# SCH_projecthackclub_2024-11-15.net
KiCad netlist of a schematic drawn in EasyEDA
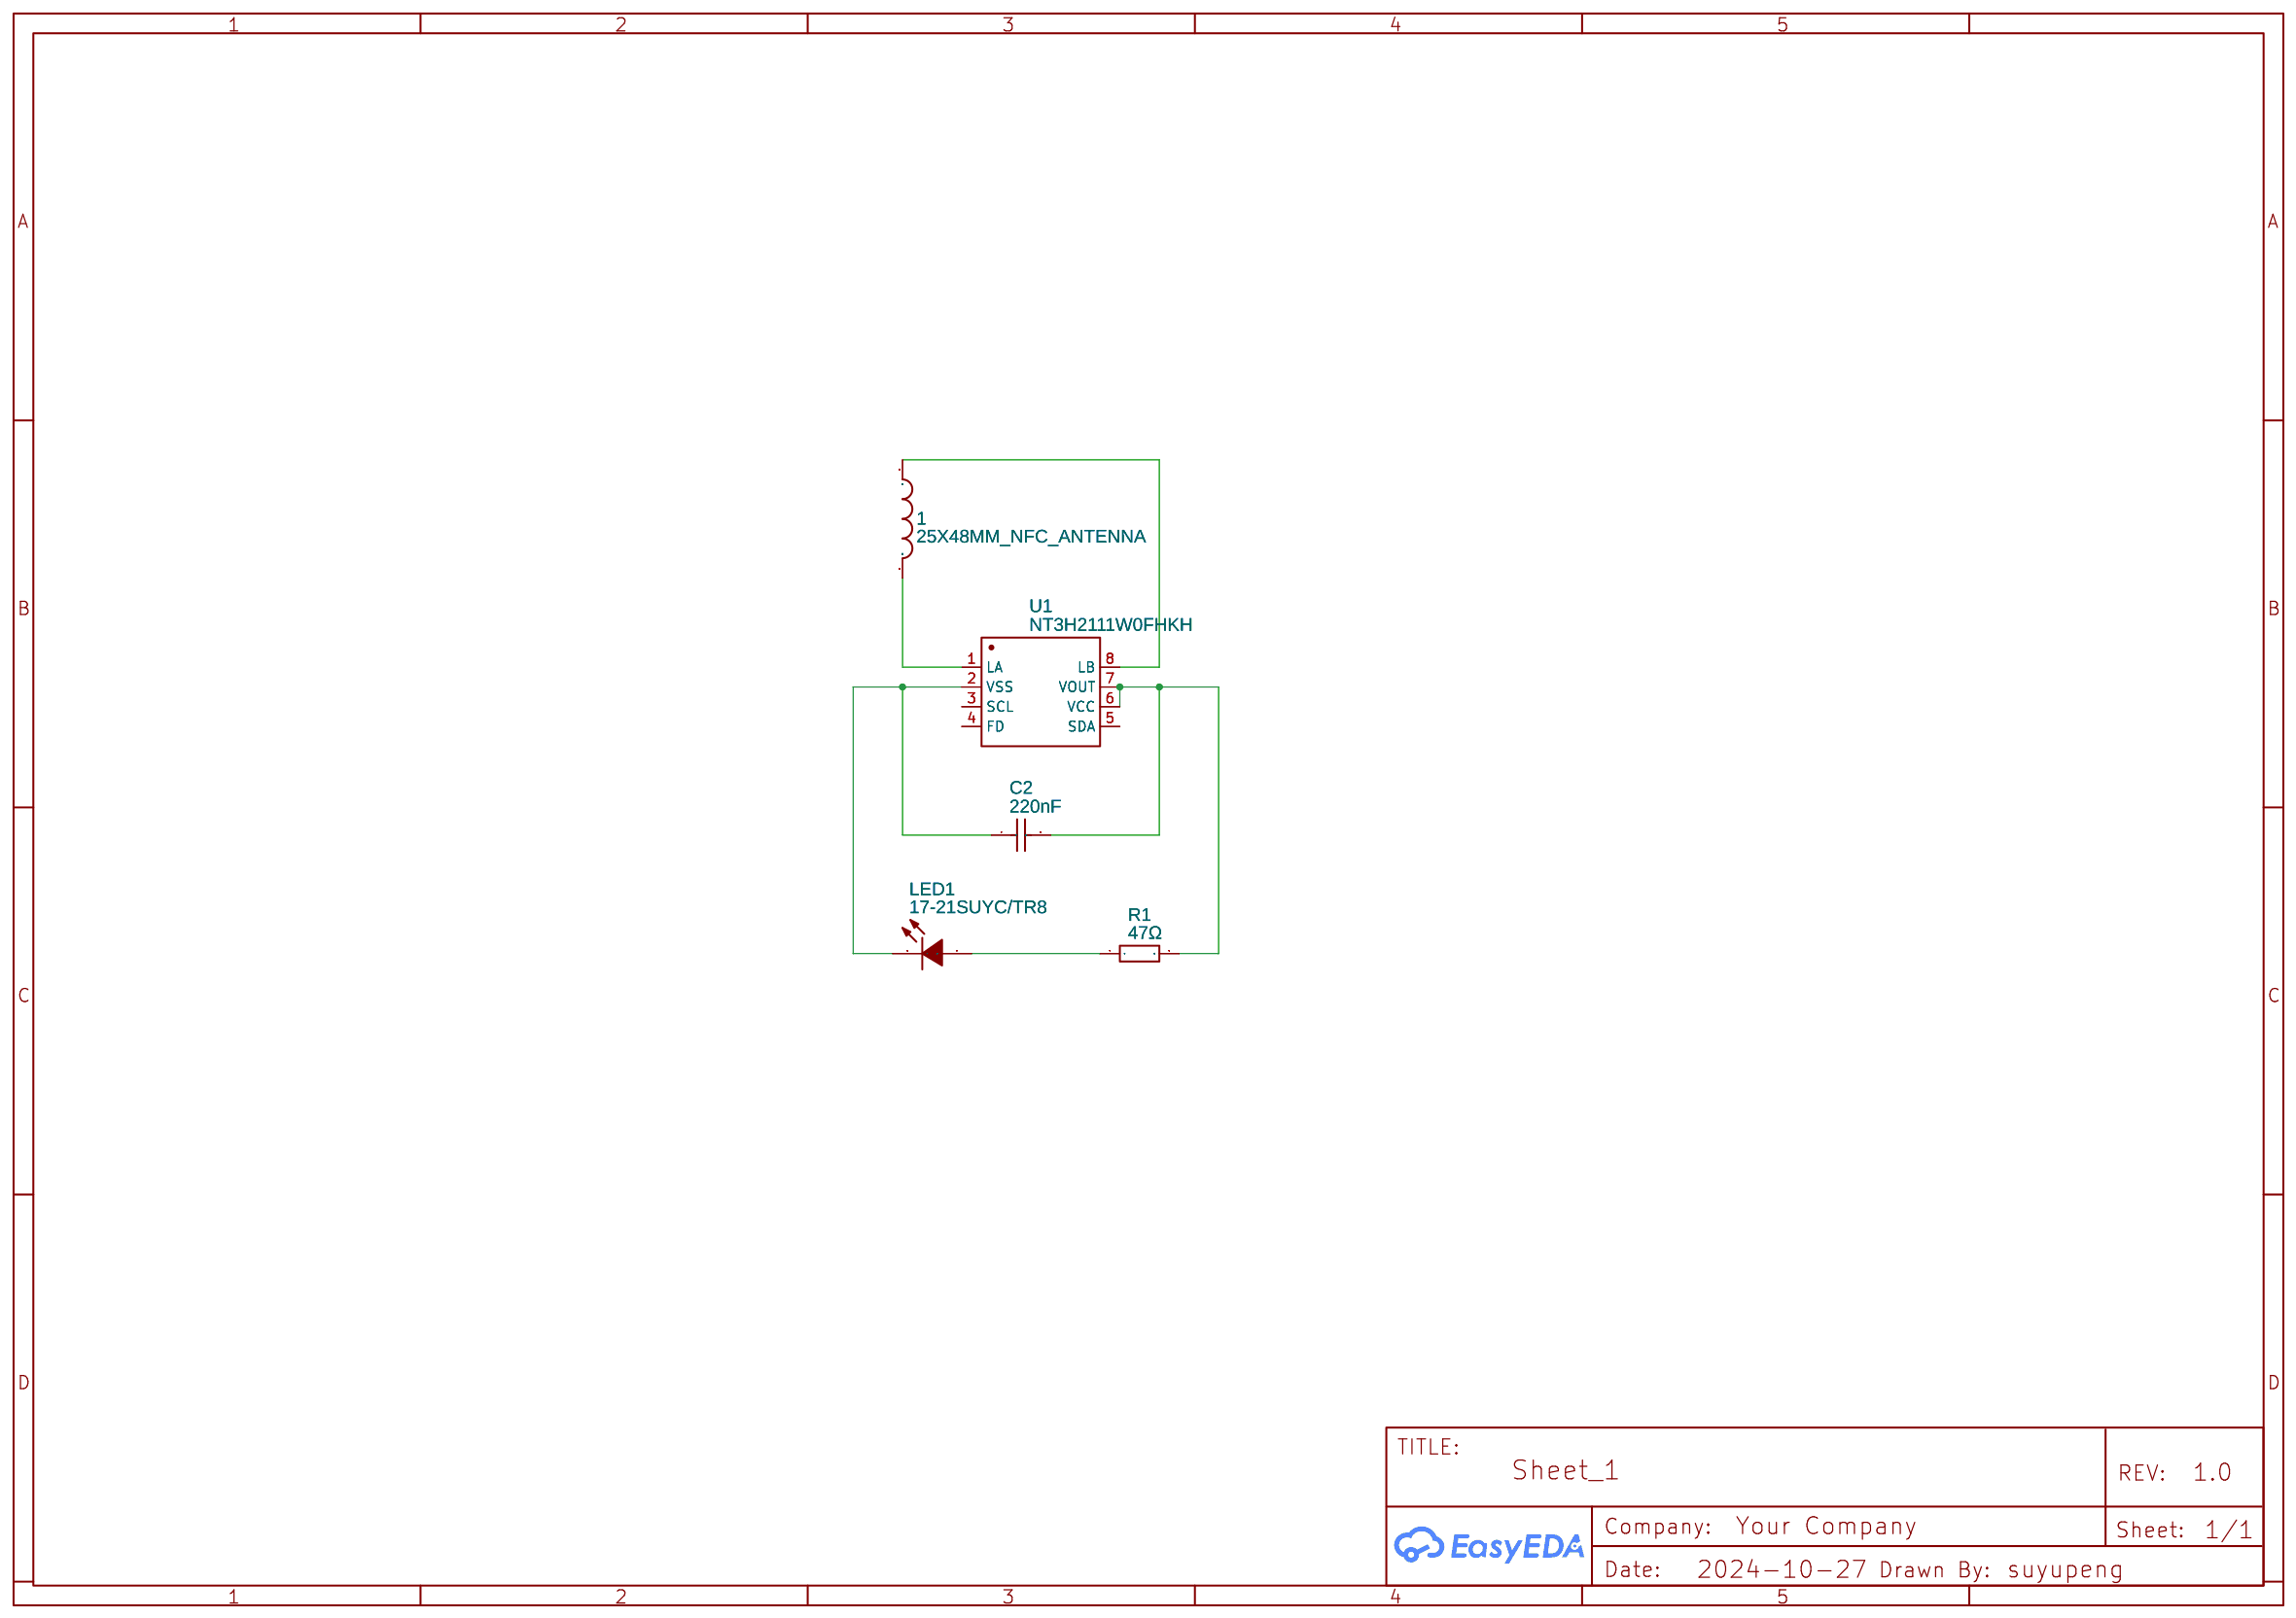
[diagram p0: schematic sheet]

(export (version "E")
  (design (tool "Eeschema 10.0.6"))
  (components
    (comp (ref "1") (value "25X48MM_NFC_ANTENNA") (libsource (lib "") (part "25X48MM_NFC_ANTENNA")))
    (comp (ref "C2")
      (value "220nF")
      (fields
        (field (name "Manufacturer Part") "CL10B224KA8NNNC")
        (field (name "Manufacturer") "SAMSUNG(三星)")
      )
      (libsource (lib "") (part "CL10B224KA8NNNC"))
    )
    (comp (ref "LED1")
      (value "17-21SUYC/TR8")
      (fields (field (name "Manufacturer Part") "KT-0805黄灯") (field (name "Manufacturer") "KENTO"))
      (libsource (lib "") (part "17-21SUYC/TR8"))
    )
    (comp (ref "R1")
      (value "47Ω")
      (fields
        (field (name "Manufacturer Part") "0603WAF470JT5E")
        (field (name "Manufacturer") "UNI-ROYAL(厚声)")
      )
      (libsource (lib "") (part "0603WAF470JT5E"))
    )
    (comp (ref "U1")
      (value "NT3H2111W0FHKH")
      (fields (field (name "Manufacturer") "NXP(恩智浦)"))
      (libsource (lib "") (part "NT3H2111W0FHKH"))
    )
  )
  (nets
    (net (code "1") (name "Net-(LED1-+)") (class "Default")
      (node (ref "LED1") (pin "1") (pinfunction "+_1") (pintype "unspecified"))
      (node (ref "R1") (pin "1") (pinfunction "1_1") (pintype "input"))
    )
    (net (code "2") (name "Net-(LED1--)") (class "Default")
      (node (ref "C2") (pin "1") (pinfunction "1_1") (pintype "input"))
      (node (ref "LED1") (pin "2") (pinfunction "-_2") (pintype "unspecified"))
      (node (ref "U1") (pin "2") (pinfunction "VSS_2") (pintype "unspecified"))
    )
    (net (code "3") (name "Net-(U1-LA)") (class "Default")
      (node (ref "1") (pin "P$2") (pinfunction "P$2_P$2") (pintype "bidirectional"))
      (node (ref "U1") (pin "1") (pinfunction "LA_1") (pintype "unspecified"))
    )
    (net (code "4") (name "Net-(U1-LB)") (class "Default")
      (node (ref "1") (pin "P$1") (pinfunction "P$1_P$1") (pintype "bidirectional"))
      (node (ref "U1") (pin "8") (pinfunction "LB_8") (pintype "unspecified"))
    )
    (net (code "5") (name "Net-(U1-VCC)") (class "Default")
      (node (ref "C2") (pin "2") (pinfunction "2_2") (pintype "input"))
      (node (ref "R1") (pin "2") (pinfunction "2_2") (pintype "input"))
      (node (ref "U1") (pin "6") (pinfunction "VCC_6") (pintype "unspecified"))
      (node (ref "U1") (pin "7") (pinfunction "VOUT_7") (pintype "unspecified"))
    )
    (net (code "6") (name "unconnected-(U1-FD-Pad4)") (class "Default")
      (node (ref "U1") (pin "4") (pinfunction "FD_4") (pintype "unspecified"))
    )
    (net (code "7") (name "unconnected-(U1-SCL-Pad3)") (class "Default")
      (node (ref "U1") (pin "3") (pinfunction "SCL_3") (pintype "unspecified"))
    )
    (net (code "8") (name "unconnected-(U1-SDA-Pad5)") (class "Default")
      (node (ref "U1") (pin "5") (pinfunction "SDA_5") (pintype "unspecified"))
    )
  )
)
